# STM32.net
KiCad netlist of a schematic drawn in Altium Designer
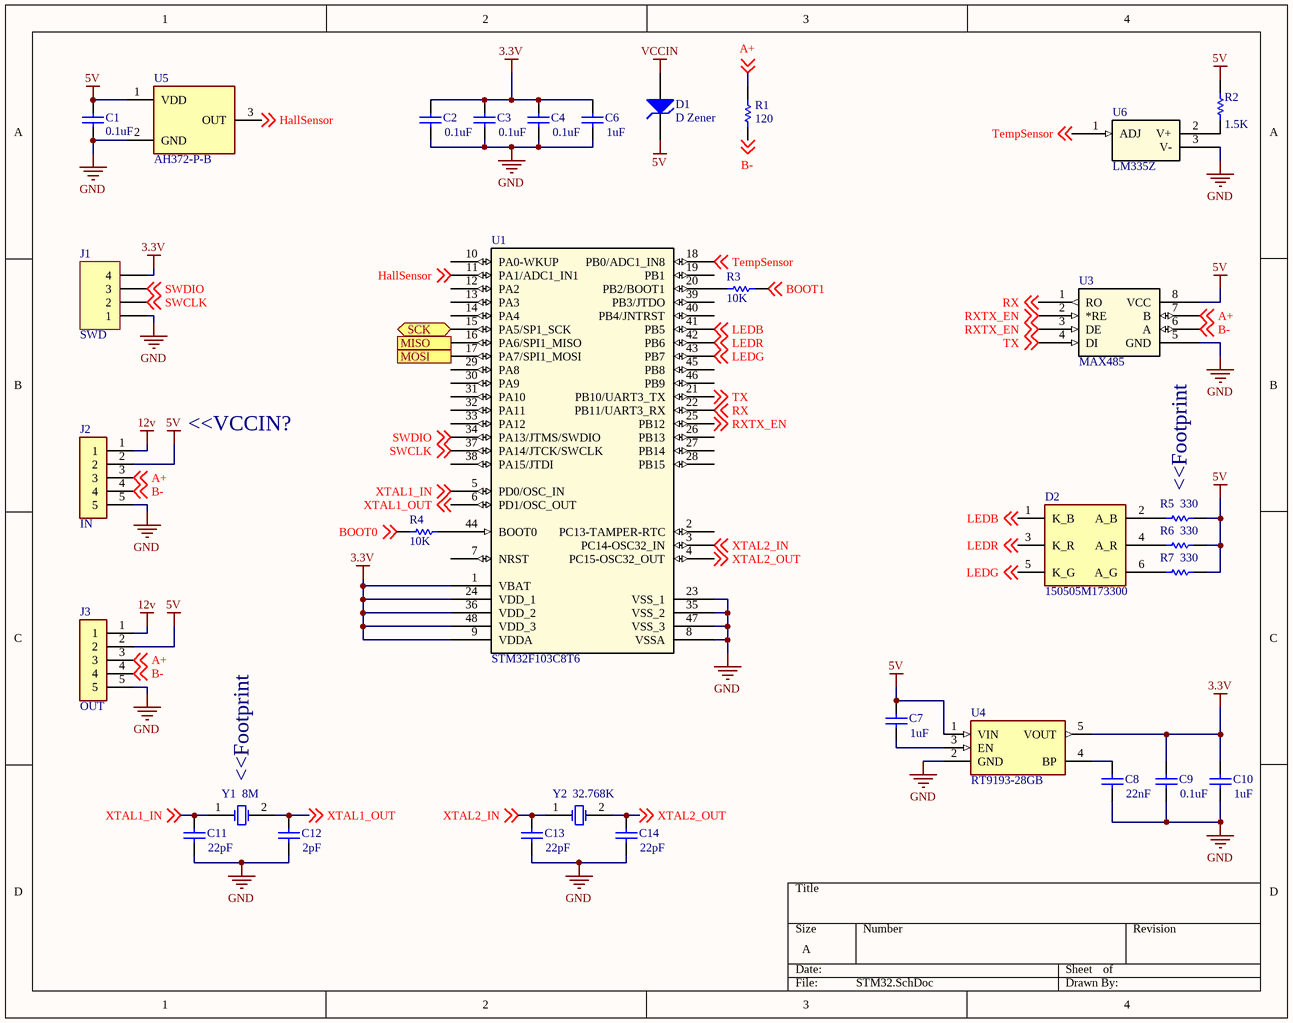
[diagram p0: STM32.SchDoc]

(export (version "E")
  (design (tool "Eeschema 10.0.6"))
  (components
    (comp (ref "C1")
      (value "0.1uF")
      (footprint "RAD-0.3")
      (description "Capacitor")
      (fields (field (name "PUBLISHER") "Altium Limited"))
      (libsource (lib "Miscellaneous Devices") (part "Cap"))
    )
    (comp (ref "C2")
      (value "0.1uF")
      (footprint "RAD-0.3")
      (description "Capacitor")
      (fields (field (name "PUBLISHER") "Altium Limited"))
      (libsource (lib "Miscellaneous Devices") (part "Cap"))
    )
    (comp (ref "C3")
      (value "0.1uF")
      (footprint "RAD-0.3")
      (description "Capacitor")
      (fields (field (name "PUBLISHER") "Altium Limited"))
      (libsource (lib "Miscellaneous Devices") (part "Cap"))
    )
    (comp (ref "C4")
      (value "0.1uF")
      (footprint "RAD-0.3")
      (description "Capacitor")
      (fields (field (name "PUBLISHER") "Altium Limited"))
      (libsource (lib "Miscellaneous Devices") (part "Cap"))
    )
    (comp (ref "C6")
      (value "1uF")
      (footprint "RAD-0.3")
      (description "Capacitor")
      (fields (field (name "PUBLISHER") "Altium Limited"))
      (libsource (lib "Miscellaneous Devices") (part "Cap"))
    )
    (comp (ref "C7")
      (value "1uF")
      (footprint "RAD-0.3")
      (description "Capacitor")
      (fields (field (name "PUBLISHER") "Altium Limited"))
      (libsource (lib "Miscellaneous Devices") (part "Cap"))
    )
    (comp (ref "C8")
      (value "22nF")
      (footprint "RAD-0.3")
      (description "Capacitor")
      (fields (field (name "PUBLISHER") "Altium Limited"))
      (libsource (lib "Miscellaneous Devices") (part "Cap"))
    )
    (comp (ref "C9")
      (value "0.1uF")
      (footprint "RAD-0.3")
      (description "Capacitor")
      (fields (field (name "PUBLISHER") "Altium Limited"))
      (libsource (lib "Miscellaneous Devices") (part "Cap"))
    )
    (comp (ref "C10")
      (value "1uF")
      (footprint "RAD-0.3")
      (description "Capacitor")
      (fields (field (name "PUBLISHER") "Altium Limited"))
      (libsource (lib "Miscellaneous Devices") (part "Cap"))
    )
    (comp (ref "C11")
      (value "22pF")
      (footprint "RAD-0.3")
      (description "Capacitor")
      (fields (field (name "PUBLISHER") "Altium Limited"))
      (libsource (lib "Miscellaneous Devices") (part "Cap"))
    )
    (comp (ref "C12")
      (value "2pF")
      (footprint "RAD-0.3")
      (description "Capacitor")
      (fields (field (name "PUBLISHER") "Altium Limited"))
      (libsource (lib "Miscellaneous Devices") (part "Cap"))
    )
    (comp (ref "C13")
      (value "22pF")
      (footprint "RAD-0.3")
      (description "Capacitor")
      (fields (field (name "PUBLISHER") "Altium Limited"))
      (libsource (lib "Miscellaneous Devices") (part "Cap"))
    )
    (comp (ref "C14")
      (value "22pF")
      (footprint "RAD-0.3")
      (description "Capacitor")
      (fields (field (name "PUBLISHER") "Altium Limited"))
      (libsource (lib "Miscellaneous Devices") (part "Cap"))
    )
    (comp (ref "D1")
      (value "D Zener")
      (footprint "DIODE-0.7")
      (description "Zener Diode")
      (fields (field (name "PUBLISHER") "Altium Limited"))
      (libsource (lib "Miscellaneous Devices") (part "D Zener"))
    )
    (comp (ref "D2")
      (value "150505M173300")
      (footprint "SamacSys:150505M173300")
      (description "LED")
      (fields
        (field (name "MOUSER PART NUMBER") "710-150505M173300")
        (field (name "RS PART NUMBER") "1766248P")
      )
      (libsource (lib "Schematic_Emile") (part "150505M173300"))
    )
    (comp (ref "J1")
      (value "SWD")
      (footprint "HDR1X4")
      (description "Header, 4-Pin")
      (fields (field (name "PUBLISHER") "Altium Limited"))
      (libsource (lib "Miscellaneous Connectors") (part "Header 4"))
    )
    (comp (ref "J2")
      (value "IN")
      (footprint "Footprint_Emile:S5BXHA1LFSN")
      (description "Connector")
      (fields (field (name "MANUFACTURER_PART_NUMBER") "S5B-XH-A-1(LF)(SN)"))
      (libsource (lib "Schematic_Emile") (part "JST 5POS"))
    )
    (comp (ref "J3")
      (value "OUT")
      (footprint "Footprint_Emile:S5BXHA1LFSN")
      (description "Connector")
      (fields (field (name "MANUFACTURER_PART_NUMBER") "S5B-XH-A-1(LF)(SN)"))
      (libsource (lib "Schematic_Emile") (part "JST 5POS"))
    )
    (comp (ref "R1")
      (value "120")
      (footprint "AXIAL-0.3")
      (description "Resistor")
      (fields (field (name "PUBLISHER") "Altium Limited"))
      (libsource (lib "Miscellaneous Devices") (part "Res1"))
    )
    (comp (ref "R2")
      (value "1.5K")
      (footprint "AXIAL-0.3")
      (description "Resistor")
      (fields (field (name "PUBLISHER") "Altium Limited"))
      (libsource (lib "Miscellaneous Devices") (part "Res1"))
    )
    (comp (ref "R3")
      (value "10K")
      (footprint "AXIAL-0.3")
      (description "Resistor")
      (fields (field (name "PUBLISHER") "Altium Limited"))
      (libsource (lib "Miscellaneous Devices") (part "Res1"))
    )
    (comp (ref "R4")
      (value "10K")
      (footprint "AXIAL-0.3")
      (description "Resistor")
      (fields (field (name "PUBLISHER") "Altium Limited"))
      (libsource (lib "Miscellaneous Devices") (part "Res1"))
    )
    (comp (ref "R5")
      (value "330")
      (footprint "AXIAL-0.3")
      (description "Resistor")
      (fields (field (name "PUBLISHER") "Altium Limited"))
      (libsource (lib "Miscellaneous Devices") (part "Res1"))
    )
    (comp (ref "R6")
      (value "330")
      (footprint "AXIAL-0.3")
      (description "Resistor")
      (fields (field (name "PUBLISHER") "Altium Limited"))
      (libsource (lib "Miscellaneous Devices") (part "Res1"))
    )
    (comp (ref "R7")
      (value "330")
      (footprint "AXIAL-0.3")
      (description "Resistor")
      (fields (field (name "PUBLISHER") "Altium Limited"))
      (libsource (lib "Miscellaneous Devices") (part "Res1"))
    )
    (comp (ref "U1")
      (value "STM32F103C8T6")
      (footprint "LQFP-48")
      (description "Integrated Circuit STM32")
      (fields (field (name "COPYRIGHT") "Copyright (C) 2018 Accelerated Designs. All rights reserved"))
      (libsource (lib "Schematic_Emile") (part "STM32F103C8T6"))
    )
    (comp (ref "U3")
      (value "MAX485")
      (footprint "21-0043D_8")
      (description "RS485 Communication")
      (fields
        (field (name "MANUFACTURER_PART_NUMBER") "MAX485CPA+")
        (field (name "COPYRIGHT") "Copyright (C) 2018 Accelerated Designs. All rights reserved")
      )
      (libsource (lib "Schematic_Emile") (part "MAX485CPA+"))
    )
    (comp (ref "U4")
      (value "RT9193-28GB")
      (footprint "SamacSys:SOT94P279X130-5N")
      (description "Voltage Regulator 3.3V")
      (libsource (lib "Schematic_Emile") (part "RT9193-28GB"))
    )
    (comp (ref "U5")
      (value "AH372-P-B")
      (footprint "SamacSys:AH372PB")
      (description "Hall Sensor")
      (fields (field (name "MOUSER PART NUMBER") "621-AH372-P-B") (field (name "RS PART NUMBER") "1333361P"))
      (libsource (lib "Schematic_Emile") (part "AH372-P-B"))
    )
    (comp (ref "U6")
      (value "LM335Z")
      (footprint "TO92")
      (description "Temperature Sensor")
      (fields (field (name "COPYRIGHT") "Copyright (C) 2018 Accelerated Designs. All rights reserved"))
      (libsource (lib "Schematic_Emile") (part "LM335Z"))
    )
    (comp (ref "Y1")
      (value "8M")
      (footprint "R38")
      (description "Crystal Oscillator")
      (fields (field (name "PUBLISHER") "Altium Limited"))
      (libsource (lib "Miscellaneous Devices") (part "XTAL"))
    )
    (comp (ref "Y2")
      (value "32.768K")
      (footprint "R38")
      (description "Crystal Oscillator")
      (fields (field (name "PUBLISHER") "Altium Limited"))
      (libsource (lib "Miscellaneous Devices") (part "XTAL"))
    )
  )
  (nets
    (net (code "1") (name "/MISO") (class "Default")
      (node (ref "U1") (pin "16") (pinfunction "PA6/SPI1_MISO_16") (pintype "bidirectional"))
    )
    (net (code "2") (name "/MOSI") (class "Default")
      (node (ref "U1") (pin "17") (pinfunction "PA7/SPI1_MOSI_17") (pintype "bidirectional"))
    )
    (net (code "3") (name "/SCK") (class "Default")
      (node (ref "U1") (pin "15") (pinfunction "PA5/SP1_SCK_15") (pintype "bidirectional"))
    )
    (net (code "4") (name "3.3V") (class "Default")
      (node (ref "C10") (pin "1") (pinfunction "1_1") (pintype "passive"))
      (node (ref "C2") (pin "1") (pinfunction "1_1") (pintype "passive"))
      (node (ref "C3") (pin "1") (pinfunction "1_1") (pintype "passive"))
      (node (ref "C4") (pin "1") (pinfunction "1_1") (pintype "passive"))
      (node (ref "C6") (pin "1") (pinfunction "1_1") (pintype "passive"))
      (node (ref "C9") (pin "1") (pinfunction "1_1") (pintype "passive"))
      (node (ref "J1") (pin "4") (pinfunction "4_4") (pintype "passive"))
      (node (ref "U1") (pin "1") (pinfunction "VBAT_1") (pintype "power_in"))
      (node (ref "U1") (pin "24") (pinfunction "VDD_1_24") (pintype "power_in"))
      (node (ref "U1") (pin "36") (pinfunction "VDD_2_36") (pintype "power_in"))
      (node (ref "U1") (pin "48") (pinfunction "VDD_3_48") (pintype "power_in"))
      (node (ref "U1") (pin "9") (pinfunction "VDDA_9") (pintype "power_in"))
      (node (ref "U4") (pin "5") (pinfunction "VOUT_5") (pintype "output"))
    )
    (net (code "5") (name "5V") (class "Default")
      (node (ref "C1") (pin "2") (pinfunction "2_2") (pintype "passive"))
      (node (ref "C7") (pin "1") (pinfunction "1_1") (pintype "passive"))
      (node (ref "D1") (pin "2") (pinfunction "K_2") (pintype "passive"))
      (node (ref "J2") (pin "2") (pinfunction "2_2") (pintype "passive"))
      (node (ref "J3") (pin "2") (pinfunction "2_2") (pintype "passive"))
      (node (ref "R2") (pin "2") (pinfunction "2_2") (pintype "passive"))
      (node (ref "R5") (pin "1") (pinfunction "1_1") (pintype "passive"))
      (node (ref "R6") (pin "1") (pinfunction "1_1") (pintype "passive"))
      (node (ref "R7") (pin "1") (pinfunction "1_1") (pintype "passive"))
      (node (ref "U3") (pin "8") (pinfunction "VCC_8") (pintype "power_in"))
      (node (ref "U4") (pin "1") (pinfunction "VIN_1") (pintype "input"))
      (node (ref "U5") (pin "1") (pinfunction "VDD_1") (pintype "passive"))
    )
    (net (code "6") (name "12v") (class "Default")
      (node (ref "J2") (pin "1") (pinfunction "1_1") (pintype "passive"))
      (node (ref "J3") (pin "1") (pinfunction "1_1") (pintype "passive"))
    )
    (net (code "7") (name "A+") (class "Default")
      (node (ref "J2") (pin "3") (pinfunction "3_3") (pintype "passive"))
      (node (ref "J3") (pin "3") (pinfunction "3_3") (pintype "passive"))
      (node (ref "R1") (pin "2") (pinfunction "2_2") (pintype "passive"))
      (node (ref "U3") (pin "7") (pinfunction "B_7") (pintype "bidirectional"))
    )
    (net (code "8") (name "B-") (class "Default")
      (node (ref "J2") (pin "4") (pinfunction "4_4") (pintype "passive"))
      (node (ref "J3") (pin "4") (pinfunction "4_4") (pintype "passive"))
      (node (ref "R1") (pin "1") (pinfunction "1_1") (pintype "passive"))
      (node (ref "U3") (pin "6") (pinfunction "A_6") (pintype "bidirectional"))
    )
    (net (code "9") (name "BOOT0") (class "Default")
      (node (ref "R4") (pin "2") (pinfunction "2_2") (pintype "passive"))
    )
    (net (code "10") (name "BOOT1") (class "Default")
      (node (ref "R3") (pin "1") (pinfunction "1_1") (pintype "passive"))
    )
    (net (code "11") (name "GND") (class "Default")
      (node (ref "C1") (pin "1") (pinfunction "1_1") (pintype "passive"))
      (node (ref "C10") (pin "2") (pinfunction "2_2") (pintype "passive"))
      (node (ref "C11") (pin "2") (pinfunction "2_2") (pintype "passive"))
      (node (ref "C12") (pin "2") (pinfunction "2_2") (pintype "passive"))
      (node (ref "C13") (pin "2") (pinfunction "2_2") (pintype "passive"))
      (node (ref "C14") (pin "2") (pinfunction "2_2") (pintype "passive"))
      (node (ref "C2") (pin "2") (pinfunction "2_2") (pintype "passive"))
      (node (ref "C3") (pin "2") (pinfunction "2_2") (pintype "passive"))
      (node (ref "C4") (pin "2") (pinfunction "2_2") (pintype "passive"))
      (node (ref "C6") (pin "2") (pinfunction "2_2") (pintype "passive"))
      (node (ref "C8") (pin "2") (pinfunction "2_2") (pintype "passive"))
      (node (ref "C9") (pin "2") (pinfunction "2_2") (pintype "passive"))
      (node (ref "J1") (pin "1") (pinfunction "1_1") (pintype "passive"))
      (node (ref "J2") (pin "5") (pinfunction "5_5") (pintype "passive"))
      (node (ref "J3") (pin "5") (pinfunction "5_5") (pintype "passive"))
      (node (ref "U1") (pin "23") (pinfunction "VSS_1_23") (pintype "power_in"))
      (node (ref "U1") (pin "35") (pinfunction "VSS_2_35") (pintype "power_in"))
      (node (ref "U1") (pin "47") (pinfunction "VSS_3_47") (pintype "power_in"))
      (node (ref "U1") (pin "8") (pinfunction "VSSA_8") (pintype "power_in"))
      (node (ref "U3") (pin "5") (pinfunction "GND_5") (pintype "power_in"))
      (node (ref "U4") (pin "2") (pinfunction "GND_2") (pintype "power_in"))
      (node (ref "U5") (pin "2") (pinfunction "GND_2") (pintype "passive"))
      (node (ref "U6") (pin "3") (pinfunction "V-_3") (pintype "power_in"))
    )
    (net (code "12") (name "HallSensor") (class "Default")
      (node (ref "U1") (pin "11") (pinfunction "PA1/ADC1_IN1_11") (pintype "bidirectional"))
      (node (ref "U5") (pin "3") (pinfunction "OUT_3") (pintype "passive"))
    )
    (net (code "13") (name "LEDB") (class "Default")
      (node (ref "D2") (pin "1") (pinfunction "K_B_1") (pintype "passive"))
      (node (ref "U1") (pin "41") (pinfunction "PB5_41") (pintype "bidirectional"))
    )
    (net (code "14") (name "LEDG") (class "Default")
      (node (ref "D2") (pin "5") (pinfunction "K_G_5") (pintype "passive"))
      (node (ref "U1") (pin "43") (pinfunction "PB7_43") (pintype "bidirectional"))
    )
    (net (code "15") (name "LEDR") (class "Default")
      (node (ref "D2") (pin "3") (pinfunction "K_R_3") (pintype "passive"))
      (node (ref "U1") (pin "42") (pinfunction "PB6_42") (pintype "bidirectional"))
    )
    (net (code "16") (name "Net-(D2-A_B)") (class "Default")
      (node (ref "D2") (pin "2") (pinfunction "A_B_2") (pintype "passive"))
      (node (ref "R5") (pin "2") (pinfunction "2_2") (pintype "passive"))
    )
    (net (code "17") (name "Net-(D2-A_G)") (class "Default")
      (node (ref "D2") (pin "6") (pinfunction "A_G_6") (pintype "passive"))
      (node (ref "R7") (pin "2") (pinfunction "2_2") (pintype "passive"))
    )
    (net (code "18") (name "Net-(D2-A_R)") (class "Default")
      (node (ref "D2") (pin "4") (pinfunction "A_R_4") (pintype "passive"))
      (node (ref "R6") (pin "2") (pinfunction "2_2") (pintype "passive"))
    )
    (net (code "19") (name "Net-(U1-BOOT0)") (class "Default")
      (node (ref "R4") (pin "1") (pinfunction "1_1") (pintype "passive"))
      (node (ref "U1") (pin "44") (pinfunction "BOOT0_44") (pintype "input"))
    )
    (net (code "20") (name "Net-(U1-PB2{slash}BOOT1)") (class "Default")
      (node (ref "R3") (pin "2") (pinfunction "2_2") (pintype "passive"))
      (node (ref "U1") (pin "20") (pinfunction "PB2/BOOT1_20") (pintype "bidirectional"))
    )
    (net (code "21") (name "Net-(U4-BP)") (class "Default")
      (node (ref "C8") (pin "1") (pinfunction "1_1") (pintype "passive"))
      (node (ref "U4") (pin "4") (pinfunction "BP_4") (pintype "passive"))
    )
    (net (code "22") (name "Net-(U4-EN)") (class "Default")
      (node (ref "C7") (pin "2") (pinfunction "2_2") (pintype "passive"))
      (node (ref "U4") (pin "3") (pinfunction "EN_3") (pintype "input"))
    )
    (net (code "23") (name "Net-(U6-V+)") (class "Default")
      (node (ref "R2") (pin "1") (pinfunction "1_1") (pintype "passive"))
      (node (ref "U6") (pin "2") (pinfunction "V+_2") (pintype "power_in"))
    )
    (net (code "24") (name "RX") (class "Default")
      (node (ref "U1") (pin "22") (pinfunction "PB11/UART3_RX_22") (pintype "bidirectional"))
      (node (ref "U3") (pin "1") (pinfunction "RO_1") (pintype "output"))
    )
    (net (code "25") (name "RXTX_EN") (class "Default")
      (node (ref "U1") (pin "25") (pinfunction "PB12_25") (pintype "bidirectional"))
      (node (ref "U3") (pin "2") (pinfunction "*RE_2") (pintype "input"))
      (node (ref "U3") (pin "3") (pinfunction "DE_3") (pintype "input"))
    )
    (net (code "26") (name "SWCLK") (class "Default")
      (node (ref "J1") (pin "2") (pinfunction "2_2") (pintype "passive"))
      (node (ref "U1") (pin "37") (pinfunction "PA14/JTCK/SWCLK_37") (pintype "bidirectional"))
    )
    (net (code "27") (name "SWDIO") (class "Default")
      (node (ref "J1") (pin "3") (pinfunction "3_3") (pintype "passive"))
      (node (ref "U1") (pin "34") (pinfunction "PA13/JTMS/SWDIO_34") (pintype "bidirectional"))
    )
    (net (code "28") (name "TX") (class "Default")
      (node (ref "U1") (pin "21") (pinfunction "PB10/UART3_TX_21") (pintype "bidirectional"))
      (node (ref "U3") (pin "4") (pinfunction "DI_4") (pintype "input"))
    )
    (net (code "29") (name "TempSensor") (class "Default")
      (node (ref "U1") (pin "18") (pinfunction "PB0/ADC1_IN8_18") (pintype "bidirectional"))
      (node (ref "U6") (pin "1") (pinfunction "ADJ_1") (pintype "input"))
    )
    (net (code "30") (name "VCCIN") (class "Default")
      (node (ref "D1") (pin "1") (pinfunction "A_1") (pintype "passive"))
    )
    (net (code "31") (name "XTAL1_IN") (class "Default")
      (node (ref "C11") (pin "1") (pinfunction "1_1") (pintype "passive"))
      (node (ref "U1") (pin "5") (pinfunction "PD0/OSC_IN_5") (pintype "bidirectional"))
      (node (ref "Y1") (pin "1") (pinfunction "OSC1_1") (pintype "passive"))
    )
    (net (code "32") (name "XTAL1_OUT") (class "Default")
      (node (ref "C12") (pin "1") (pinfunction "1_1") (pintype "passive"))
      (node (ref "U1") (pin "6") (pinfunction "PD1/OSC_OUT_6") (pintype "bidirectional"))
      (node (ref "Y1") (pin "2") (pinfunction "OSC2_2") (pintype "passive"))
    )
    (net (code "33") (name "XTAL2_IN") (class "Default")
      (node (ref "C13") (pin "1") (pinfunction "1_1") (pintype "passive"))
      (node (ref "U1") (pin "3") (pinfunction "PC14-OSC32_IN_3") (pintype "bidirectional"))
      (node (ref "Y2") (pin "1") (pinfunction "OSC1_1") (pintype "passive"))
    )
    (net (code "34") (name "XTAL2_OUT") (class "Default")
      (node (ref "C14") (pin "1") (pinfunction "1_1") (pintype "passive"))
      (node (ref "U1") (pin "4") (pinfunction "PC15-OSC32_OUT_4") (pintype "bidirectional"))
      (node (ref "Y2") (pin "2") (pinfunction "OSC2_2") (pintype "passive"))
    )
    (net (code "35") (name "unconnected-(U1-NRST-Pad7)") (class "Default")
      (node (ref "U1") (pin "7") (pinfunction "NRST_7") (pintype "bidirectional"))
    )
    (net (code "36") (name "unconnected-(U1-PA0-WKUP-Pad10)") (class "Default")
      (node (ref "U1") (pin "10") (pinfunction "PA0-WKUP_10") (pintype "bidirectional"))
    )
    (net (code "37") (name "unconnected-(U1-PA2-Pad12)") (class "Default")
      (node (ref "U1") (pin "12") (pinfunction "PA2_12") (pintype "bidirectional"))
    )
    (net (code "38") (name "unconnected-(U1-PA3-Pad13)") (class "Default")
      (node (ref "U1") (pin "13") (pinfunction "PA3_13") (pintype "bidirectional"))
    )
    (net (code "39") (name "unconnected-(U1-PA4-Pad14)") (class "Default")
      (node (ref "U1") (pin "14") (pinfunction "PA4_14") (pintype "bidirectional"))
    )
    (net (code "40") (name "unconnected-(U1-PA8-Pad29)") (class "Default")
      (node (ref "U1") (pin "29") (pinfunction "PA8_29") (pintype "bidirectional"))
    )
    (net (code "41") (name "unconnected-(U1-PA9-Pad30)") (class "Default")
      (node (ref "U1") (pin "30") (pinfunction "PA9_30") (pintype "bidirectional"))
    )
    (net (code "42") (name "unconnected-(U1-PA10-Pad31)") (class "Default")
      (node (ref "U1") (pin "31") (pinfunction "PA10_31") (pintype "bidirectional"))
    )
    (net (code "43") (name "unconnected-(U1-PA11-Pad32)") (class "Default")
      (node (ref "U1") (pin "32") (pinfunction "PA11_32") (pintype "bidirectional"))
    )
    (net (code "44") (name "unconnected-(U1-PA12-Pad33)") (class "Default")
      (node (ref "U1") (pin "33") (pinfunction "PA12_33") (pintype "bidirectional"))
    )
    (net (code "45") (name "unconnected-(U1-PA15{slash}JTDI-Pad38)") (class "Default")
      (node (ref "U1") (pin "38") (pinfunction "PA15/JTDI_38") (pintype "bidirectional"))
    )
    (net (code "46") (name "unconnected-(U1-PB1-Pad19)") (class "Default")
      (node (ref "U1") (pin "19") (pinfunction "PB1_19") (pintype "bidirectional"))
    )
    (net (code "47") (name "unconnected-(U1-PB3{slash}JTDO-Pad39)") (class "Default")
      (node (ref "U1") (pin "39") (pinfunction "PB3/JTDO_39") (pintype "bidirectional"))
    )
    (net (code "48") (name "unconnected-(U1-PB4{slash}JNTRST-Pad40)") (class "Default")
      (node (ref "U1") (pin "40") (pinfunction "PB4/JNTRST_40") (pintype "bidirectional"))
    )
    (net (code "49") (name "unconnected-(U1-PB8-Pad45)") (class "Default")
      (node (ref "U1") (pin "45") (pinfunction "PB8_45") (pintype "bidirectional"))
    )
    (net (code "50") (name "unconnected-(U1-PB9-Pad46)") (class "Default")
      (node (ref "U1") (pin "46") (pinfunction "PB9_46") (pintype "bidirectional"))
    )
    (net (code "51") (name "unconnected-(U1-PB13-Pad26)") (class "Default")
      (node (ref "U1") (pin "26") (pinfunction "PB13_26") (pintype "bidirectional"))
    )
    (net (code "52") (name "unconnected-(U1-PB14-Pad27)") (class "Default")
      (node (ref "U1") (pin "27") (pinfunction "PB14_27") (pintype "bidirectional"))
    )
    (net (code "53") (name "unconnected-(U1-PB15-Pad28)") (class "Default")
      (node (ref "U1") (pin "28") (pinfunction "PB15_28") (pintype "bidirectional"))
    )
    (net (code "54") (name "unconnected-(U1-PC13-TAMPER-RTC-Pad2)") (class "Default")
      (node (ref "U1") (pin "2") (pinfunction "PC13-TAMPER-RTC_2") (pintype "bidirectional"))
    )
  )
)
